# PWR_ICs.net
KiCad netlist of a schematic drawn in Altium Designer
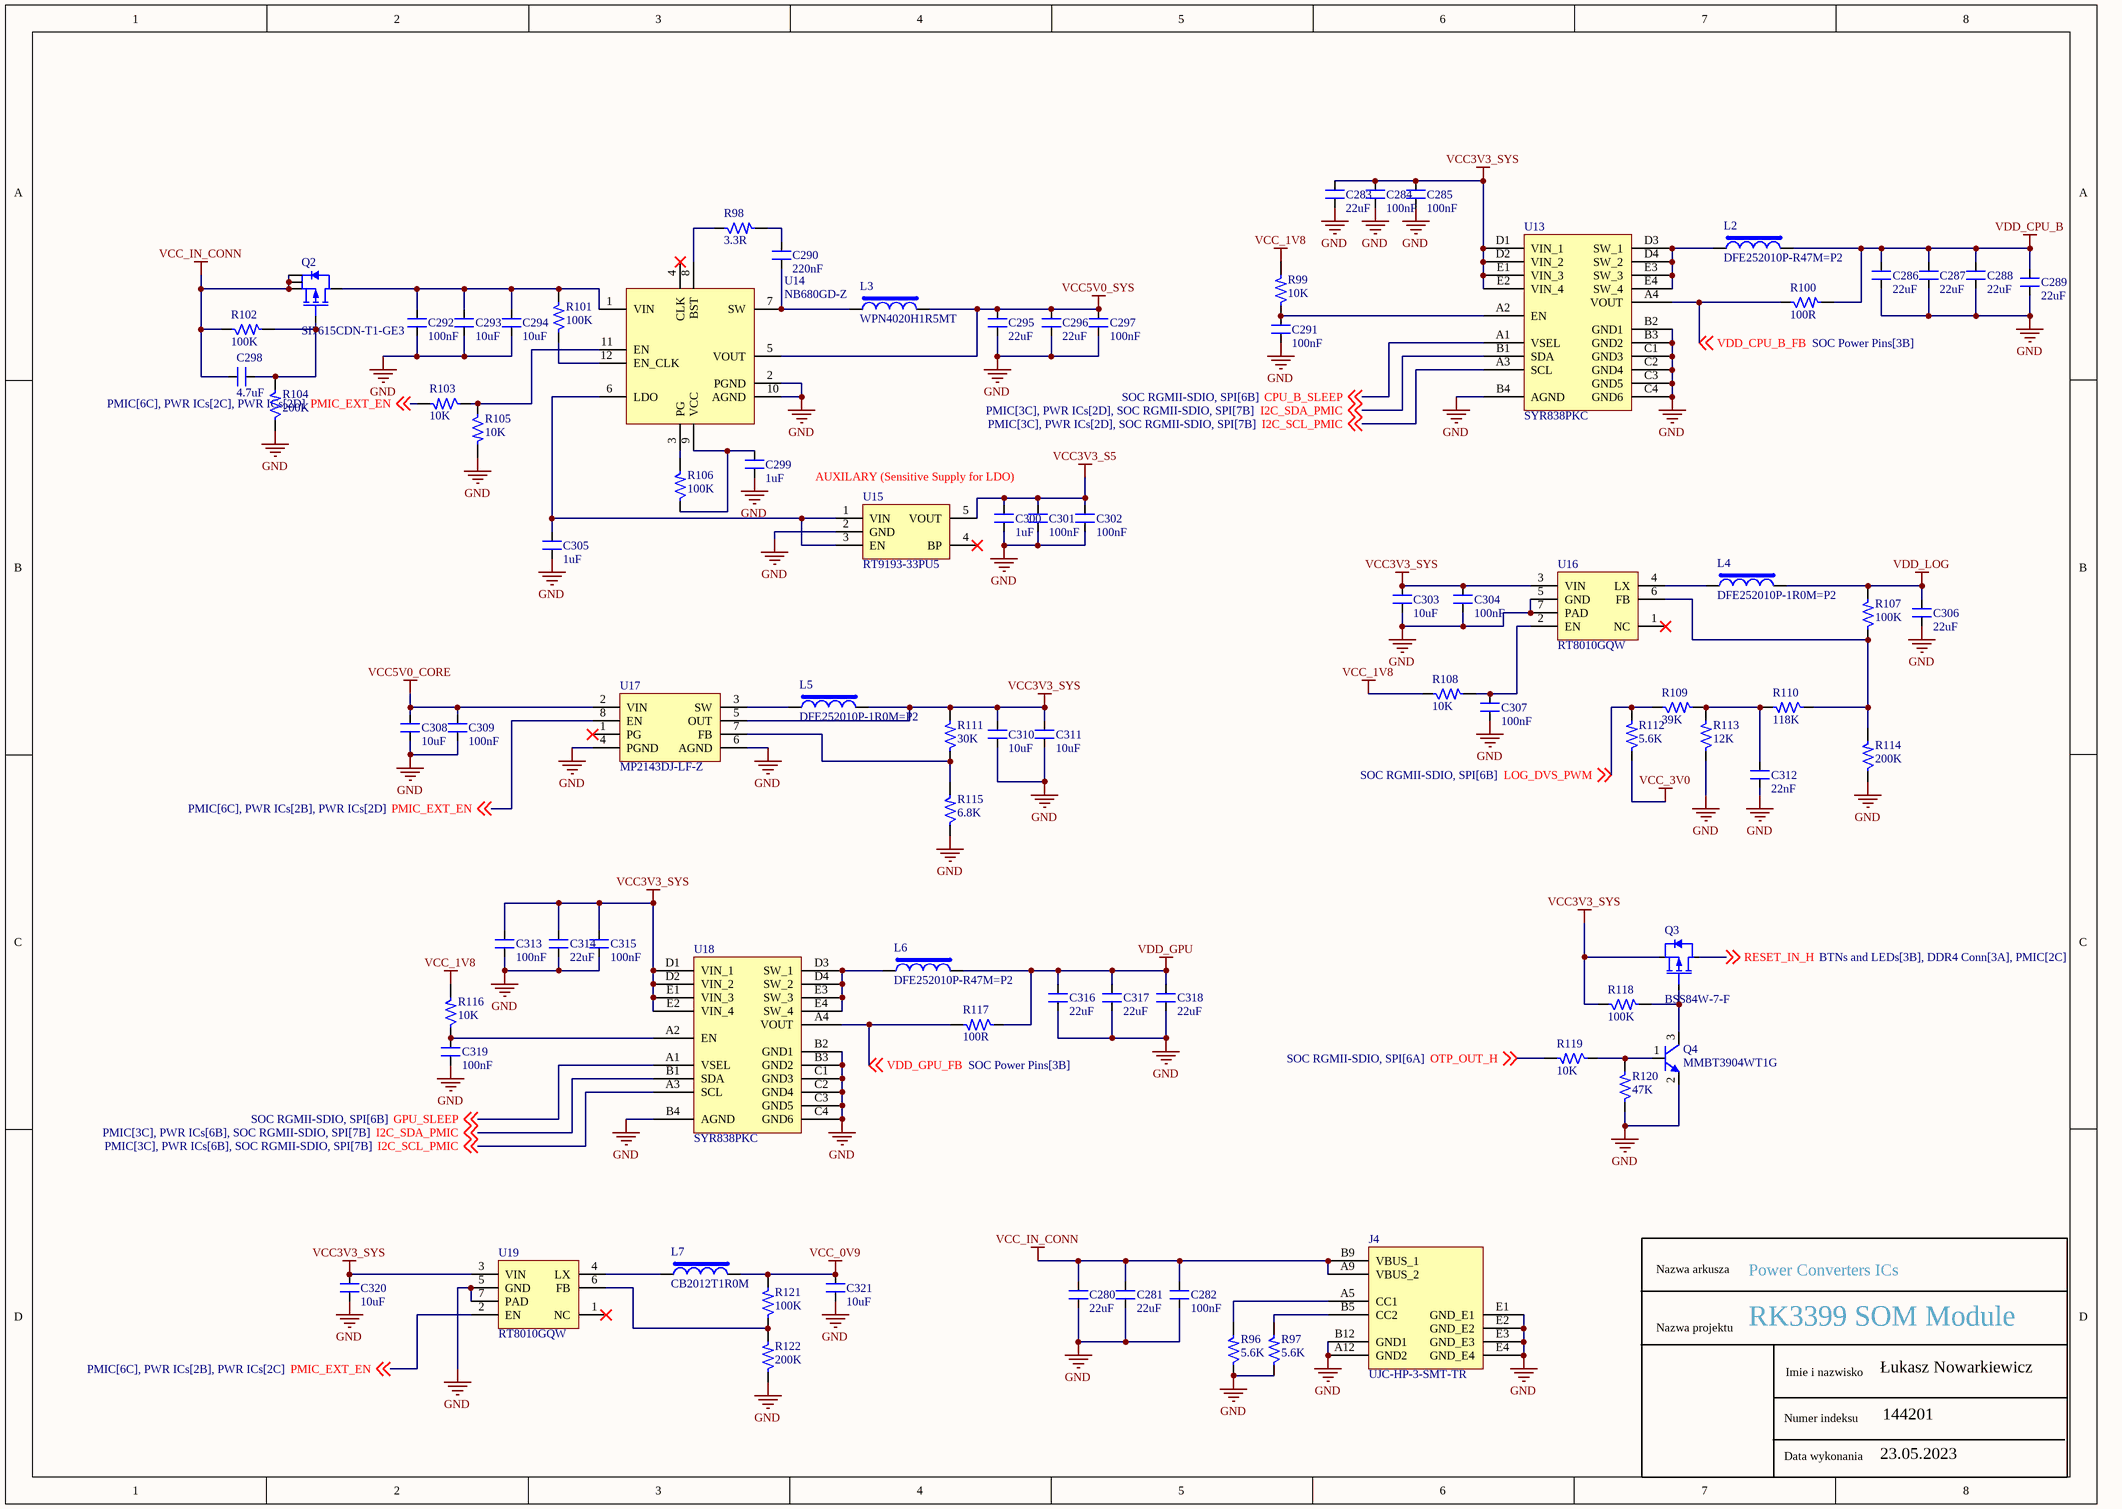
[diagram p0: PWR ICs.SchDoc]

(export (version "E")
  (design (tool "Eeschema 10.0.6"))
  (components
    (comp (ref "C280")
      (value "22uF")
      (footprint "CAP_0603")
      (description "22µF ±20% 10V Ceramic Capacitor X5R 0603 (1608 Metric)")
      (fields
        (field (name "MANUFACTURER") "Murata Electronics")
        (field (name "MANUFACTURER PART NUMBER") "GRM188R61A226ME15D")
      )
      (libsource (lib "RK3399 _Module_Schlib") (part "CAP_22uF-10V-20%-0603"))
    )
    (comp (ref "C281")
      (value "22uF")
      (footprint "CAP_0603")
      (description "22µF ±20% 10V Ceramic Capacitor X5R 0603 (1608 Metric)")
      (fields
        (field (name "MANUFACTURER") "Murata Electronics")
        (field (name "MANUFACTURER PART NUMBER") "GRM188R61A226ME15D")
      )
      (libsource (lib "RK3399 _Module_Schlib") (part "CAP_22uF-10V-20%-0603"))
    )
    (comp (ref "C282")
      (value "100nF")
      (footprint "CAP_0402")
      (description "0.1µF ±10% 25V Ceramic Capacitor X7R 0402 (1005 Metric)")
      (fields
        (field (name "MANUFACTURER") "Walsin Technology Corporation")
        (field (name "MANUFACTURER PART NUMBER") "0402B104K250CT")
      )
      (libsource (lib "RK3399 _Module_Schlib") (part "CAP_100nF-25V-10%-0402"))
    )
    (comp (ref "C283")
      (value "22uF")
      (footprint "CAP_0603")
      (description "22µF ±20% 10V Ceramic Capacitor X5R 0603 (1608 Metric)")
      (fields
        (field (name "MANUFACTURER") "Murata Electronics")
        (field (name "MANUFACTURER PART NUMBER") "GRM188R61A226ME15D")
      )
      (libsource (lib "RK3399 _Module_Schlib") (part "CAP_22uF-10V-20%-0603"))
    )
    (comp (ref "C284")
      (value "100nF")
      (footprint "CAP_0402")
      (description "0.1µF ±10% 25V Ceramic Capacitor X7R 0402 (1005 Metric)")
      (fields
        (field (name "MANUFACTURER") "Walsin Technology Corporation")
        (field (name "MANUFACTURER PART NUMBER") "0402B104K250CT")
      )
      (libsource (lib "RK3399 _Module_Schlib") (part "CAP_100nF-25V-10%-0402"))
    )
    (comp (ref "C285")
      (value "100nF")
      (footprint "CAP_0402")
      (description "0.1µF ±10% 25V Ceramic Capacitor X7R 0402 (1005 Metric)")
      (fields
        (field (name "MANUFACTURER") "Walsin Technology Corporation")
        (field (name "MANUFACTURER PART NUMBER") "0402B104K250CT")
      )
      (libsource (lib "RK3399 _Module_Schlib") (part "CAP_100nF-25V-10%-0402"))
    )
    (comp (ref "C286")
      (value "22uF")
      (footprint "CAP_0603")
      (description "22µF ±20% 10V Ceramic Capacitor X5R 0603 (1608 Metric)")
      (fields
        (field (name "MANUFACTURER") "Murata Electronics")
        (field (name "MANUFACTURER PART NUMBER") "GRM188R61A226ME15D")
      )
      (libsource (lib "RK3399 _Module_Schlib") (part "CAP_22uF-10V-20%-0603"))
    )
    (comp (ref "C287")
      (value "22uF")
      (footprint "CAP_0603")
      (description "22µF ±20% 10V Ceramic Capacitor X5R 0603 (1608 Metric)")
      (fields
        (field (name "MANUFACTURER") "Murata Electronics")
        (field (name "MANUFACTURER PART NUMBER") "GRM188R61A226ME15D")
      )
      (libsource (lib "RK3399 _Module_Schlib") (part "CAP_22uF-10V-20%-0603"))
    )
    (comp (ref "C288")
      (value "22uF")
      (footprint "CAP_0603")
      (description "22µF ±20% 10V Ceramic Capacitor X5R 0603 (1608 Metric)")
      (fields
        (field (name "MANUFACTURER") "Murata Electronics")
        (field (name "MANUFACTURER PART NUMBER") "GRM188R61A226ME15D")
      )
      (libsource (lib "RK3399 _Module_Schlib") (part "CAP_22uF-10V-20%-0603"))
    )
    (comp (ref "C289")
      (value "22uF")
      (footprint "CAP_0603")
      (description "22µF ±20% 10V Ceramic Capacitor X5R 0603 (1608 Metric)")
      (fields
        (field (name "MANUFACTURER") "Murata Electronics")
        (field (name "MANUFACTURER PART NUMBER") "GRM188R61A226ME15D")
      )
      (libsource (lib "RK3399 _Module_Schlib") (part "CAP_22uF-10V-20%-0603"))
    )
    (comp (ref "C290")
      (value "220nF")
      (footprint "CAP_0402")
      (description "0.22µF ±10% 10V Ceramic Capacitor X7R 0402 (1005 Metric)")
      (fields
        (field (name "MANUFACTURER") "Samsung Electro-Mechanics")
        (field (name "MANUFACTURER PART NUMBER") "CL05B224KP5NNNC")
      )
      (libsource (lib "RK3399 _Module_Schlib") (part "CAP_220nF-10V-10%-0402"))
    )
    (comp (ref "C291")
      (value "100nF")
      (footprint "CAP_0402")
      (description "0.1µF ±10% 25V Ceramic Capacitor X7R 0402 (1005 Metric)")
      (fields
        (field (name "MANUFACTURER") "Walsin Technology Corporation")
        (field (name "MANUFACTURER PART NUMBER") "0402B104K250CT")
      )
      (libsource (lib "RK3399 _Module_Schlib") (part "CAP_100nF-25V-10%-0402"))
    )
    (comp (ref "C292")
      (value "100nF")
      (footprint "CAP_0402")
      (description "0.1µF ±10% 25V Ceramic Capacitor X7R 0402 (1005 Metric)")
      (fields
        (field (name "MANUFACTURER") "Walsin Technology Corporation")
        (field (name "MANUFACTURER PART NUMBER") "0402B104K250CT")
      )
      (libsource (lib "RK3399 _Module_Schlib") (part "CAP_100nF-25V-10%-0402"))
    )
    (comp (ref "C293")
      (value "10uF")
      (footprint "CAP_0402")
      (description "10µF ±20% 10V Ceramic Capacitor X5R 0402 (1005 Metric)")
      (fields
        (field (name "MANUFACTURER PART NUMBER") "CL05A106MP5NUNC")
        (field (name "MANUFACTURER") "Samsung Electro-Mechanics")
      )
      (libsource (lib "RK3399 _Module_Schlib") (part "CAP_10uF-10V-20%-0402"))
    )
    (comp (ref "C294")
      (value "10uF")
      (footprint "CAP_0402")
      (description "10µF ±20% 10V Ceramic Capacitor X5R 0402 (1005 Metric)")
      (fields
        (field (name "MANUFACTURER PART NUMBER") "CL05A106MP5NUNC")
        (field (name "MANUFACTURER") "Samsung Electro-Mechanics")
      )
      (libsource (lib "RK3399 _Module_Schlib") (part "CAP_10uF-10V-20%-0402"))
    )
    (comp (ref "C295")
      (value "22uF")
      (footprint "CAP_0603")
      (description "22µF ±20% 10V Ceramic Capacitor X5R 0603 (1608 Metric)")
      (fields
        (field (name "MANUFACTURER") "Murata Electronics")
        (field (name "MANUFACTURER PART NUMBER") "GRM188R61A226ME15D")
      )
      (libsource (lib "RK3399 _Module_Schlib") (part "CAP_22uF-10V-20%-0603"))
    )
    (comp (ref "C296")
      (value "22uF")
      (footprint "CAP_0603")
      (description "22µF ±20% 10V Ceramic Capacitor X5R 0603 (1608 Metric)")
      (fields
        (field (name "MANUFACTURER") "Murata Electronics")
        (field (name "MANUFACTURER PART NUMBER") "GRM188R61A226ME15D")
      )
      (libsource (lib "RK3399 _Module_Schlib") (part "CAP_22uF-10V-20%-0603"))
    )
    (comp (ref "C297")
      (value "100nF")
      (footprint "CAP_0402")
      (description "0.1µF ±10% 25V Ceramic Capacitor X7R 0402 (1005 Metric)")
      (fields
        (field (name "MANUFACTURER") "Walsin Technology Corporation")
        (field (name "MANUFACTURER PART NUMBER") "0402B104K250CT")
      )
      (libsource (lib "RK3399 _Module_Schlib") (part "CAP_100nF-25V-10%-0402"))
    )
    (comp (ref "C298")
      (value "4.7uF")
      (footprint "CAP_0402")
      (description "4.7µF ±10% 10V Ceramic Capacitor X5R 0402 (1005 Metric)")
      (fields
        (field (name "MANUFACTURER") "Samsung Electro-Mechanics")
        (field (name "MANUFACTURER PART NUMBER") "CL05A475KP5NRNC")
      )
      (libsource (lib "RK3399 _Module_Schlib") (part "CAP_4.7uF-10V-10%-0402"))
    )
    (comp (ref "C299")
      (value "1uF")
      (footprint "CAP_0402")
      (description "1µF ±10% 16V Ceramic Capacitor X5R 0402 (1005 Metric)")
      (fields
        (field (name "MANUFACTURER") "Knowles Novacap")
        (field (name "MANUFACTURER PART NUMBER") "0402BW105K160YT")
      )
      (libsource (lib "RK3399 _Module_Schlib") (part "CAP_1uF-16V-10%-0402"))
    )
    (comp (ref "C300")
      (value "1uF")
      (footprint "CAP_0402")
      (description "1µF ±10% 16V Ceramic Capacitor X5R 0402 (1005 Metric)")
      (fields
        (field (name "MANUFACTURER") "Knowles Novacap")
        (field (name "MANUFACTURER PART NUMBER") "0402BW105K160YT")
      )
      (libsource (lib "RK3399 _Module_Schlib") (part "CAP_1uF-16V-10%-0402"))
    )
    (comp (ref "C301")
      (value "100nF")
      (footprint "CAP_0402")
      (description "0.1µF ±10% 25V Ceramic Capacitor X7R 0402 (1005 Metric)")
      (fields
        (field (name "MANUFACTURER") "Walsin Technology Corporation")
        (field (name "MANUFACTURER PART NUMBER") "0402B104K250CT")
      )
      (libsource (lib "RK3399 _Module_Schlib") (part "CAP_100nF-25V-10%-0402"))
    )
    (comp (ref "C302")
      (value "100nF")
      (footprint "CAP_0402")
      (description "0.1µF ±10% 25V Ceramic Capacitor X7R 0402 (1005 Metric)")
      (fields
        (field (name "MANUFACTURER") "Walsin Technology Corporation")
        (field (name "MANUFACTURER PART NUMBER") "0402B104K250CT")
      )
      (libsource (lib "RK3399 _Module_Schlib") (part "CAP_100nF-25V-10%-0402"))
    )
    (comp (ref "C303")
      (value "10uF")
      (footprint "CAP_0402")
      (description "10µF ±20% 10V Ceramic Capacitor X5R 0402 (1005 Metric)")
      (fields
        (field (name "MANUFACTURER PART NUMBER") "CL05A106MP5NUNC")
        (field (name "MANUFACTURER") "Samsung Electro-Mechanics")
      )
      (libsource (lib "RK3399 _Module_Schlib") (part "CAP_10uF-10V-20%-0402"))
    )
    (comp (ref "C304")
      (value "100nF")
      (footprint "CAP_0402")
      (description "0.1µF ±10% 25V Ceramic Capacitor X7R 0402 (1005 Metric)")
      (fields
        (field (name "MANUFACTURER") "Walsin Technology Corporation")
        (field (name "MANUFACTURER PART NUMBER") "0402B104K250CT")
      )
      (libsource (lib "RK3399 _Module_Schlib") (part "CAP_100nF-25V-10%-0402"))
    )
    (comp (ref "C305")
      (value "1uF")
      (footprint "CAP_0402")
      (description "1µF ±10% 16V Ceramic Capacitor X5R 0402 (1005 Metric)")
      (fields
        (field (name "MANUFACTURER") "Knowles Novacap")
        (field (name "MANUFACTURER PART NUMBER") "0402BW105K160YT")
      )
      (libsource (lib "RK3399 _Module_Schlib") (part "CAP_1uF-16V-10%-0402"))
    )
    (comp (ref "C306")
      (value "22uF")
      (footprint "CAP_0603")
      (description "22µF ±20% 10V Ceramic Capacitor X5R 0603 (1608 Metric)")
      (fields
        (field (name "MANUFACTURER") "Murata Electronics")
        (field (name "MANUFACTURER PART NUMBER") "GRM188R61A226ME15D")
      )
      (libsource (lib "RK3399 _Module_Schlib") (part "CAP_22uF-10V-20%-0603"))
    )
    (comp (ref "C307")
      (value "100nF")
      (footprint "CAP_0402")
      (description "0.1µF ±10% 25V Ceramic Capacitor X7R 0402 (1005 Metric)")
      (fields
        (field (name "MANUFACTURER") "Walsin Technology Corporation")
        (field (name "MANUFACTURER PART NUMBER") "0402B104K250CT")
      )
      (libsource (lib "RK3399 _Module_Schlib") (part "CAP_100nF-25V-10%-0402"))
    )
    (comp (ref "C308")
      (value "10uF")
      (footprint "CAP_0402")
      (description "10µF ±20% 10V Ceramic Capacitor X5R 0402 (1005 Metric)")
      (fields
        (field (name "MANUFACTURER PART NUMBER") "CL05A106MP5NUNC")
        (field (name "MANUFACTURER") "Samsung Electro-Mechanics")
      )
      (libsource (lib "RK3399 _Module_Schlib") (part "CAP_10uF-10V-20%-0402"))
    )
    (comp (ref "C309")
      (value "100nF")
      (footprint "CAP_0402")
      (description "0.1µF ±10% 25V Ceramic Capacitor X7R 0402 (1005 Metric)")
      (fields
        (field (name "MANUFACTURER") "Walsin Technology Corporation")
        (field (name "MANUFACTURER PART NUMBER") "0402B104K250CT")
      )
      (libsource (lib "RK3399 _Module_Schlib") (part "CAP_100nF-25V-10%-0402"))
    )
    (comp (ref "C310")
      (value "10uF")
      (footprint "CAP_0402")
      (description "10µF ±20% 10V Ceramic Capacitor X5R 0402 (1005 Metric)")
      (fields
        (field (name "MANUFACTURER PART NUMBER") "CL05A106MP5NUNC")
        (field (name "MANUFACTURER") "Samsung Electro-Mechanics")
      )
      (libsource (lib "RK3399 _Module_Schlib") (part "CAP_10uF-10V-20%-0402"))
    )
    (comp (ref "C311")
      (value "10uF")
      (footprint "CAP_0402")
      (description "10µF ±20% 10V Ceramic Capacitor X5R 0402 (1005 Metric)")
      (fields
        (field (name "MANUFACTURER PART NUMBER") "CL05A106MP5NUNC")
        (field (name "MANUFACTURER") "Samsung Electro-Mechanics")
      )
      (libsource (lib "RK3399 _Module_Schlib") (part "CAP_10uF-10V-20%-0402"))
    )
    (comp (ref "C312")
      (value "22nF")
      (footprint "CAP_0402")
      (description "0.022µF ±10% 10V Ceramic Capacitor X7R 0402 (1005 Metric)")
      (fields
        (field (name "MANUFACTURER") "Samsung Electro-Mechanics")
        (field (name "MANUFACTURER PART NUMBER") "CL05B223KP5NNNC")
      )
      (libsource (lib "RK3399 _Module_Schlib") (part "CAP_22nF-10V-10%-0402"))
    )
    (comp (ref "C313")
      (value "100nF")
      (footprint "CAP_0402")
      (description "0.1µF ±10% 25V Ceramic Capacitor X7R 0402 (1005 Metric)")
      (fields
        (field (name "MANUFACTURER") "Walsin Technology Corporation")
        (field (name "MANUFACTURER PART NUMBER") "0402B104K250CT")
      )
      (libsource (lib "RK3399 _Module_Schlib") (part "CAP_100nF-25V-10%-0402"))
    )
    (comp (ref "C314")
      (value "22uF")
      (footprint "CAP_0603")
      (description "22µF ±20% 10V Ceramic Capacitor X5R 0603 (1608 Metric)")
      (fields
        (field (name "MANUFACTURER") "Murata Electronics")
        (field (name "MANUFACTURER PART NUMBER") "GRM188R61A226ME15D")
      )
      (libsource (lib "RK3399 _Module_Schlib") (part "CAP_22uF-10V-20%-0603"))
    )
    (comp (ref "C315")
      (value "100nF")
      (footprint "CAP_0402")
      (description "0.1µF ±10% 25V Ceramic Capacitor X7R 0402 (1005 Metric)")
      (fields
        (field (name "MANUFACTURER") "Walsin Technology Corporation")
        (field (name "MANUFACTURER PART NUMBER") "0402B104K250CT")
      )
      (libsource (lib "RK3399 _Module_Schlib") (part "CAP_100nF-25V-10%-0402"))
    )
    (comp (ref "C316")
      (value "22uF")
      (footprint "CAP_0603")
      (description "22µF ±20% 10V Ceramic Capacitor X5R 0603 (1608 Metric)")
      (fields
        (field (name "MANUFACTURER") "Murata Electronics")
        (field (name "MANUFACTURER PART NUMBER") "GRM188R61A226ME15D")
      )
      (libsource (lib "RK3399 _Module_Schlib") (part "CAP_22uF-10V-20%-0603"))
    )
    (comp (ref "C317")
      (value "22uF")
      (footprint "CAP_0603")
      (description "22µF ±20% 10V Ceramic Capacitor X5R 0603 (1608 Metric)")
      (fields
        (field (name "MANUFACTURER") "Murata Electronics")
        (field (name "MANUFACTURER PART NUMBER") "GRM188R61A226ME15D")
      )
      (libsource (lib "RK3399 _Module_Schlib") (part "CAP_22uF-10V-20%-0603"))
    )
    (comp (ref "C318")
      (value "22uF")
      (footprint "CAP_0603")
      (description "22µF ±20% 10V Ceramic Capacitor X5R 0603 (1608 Metric)")
      (fields
        (field (name "MANUFACTURER") "Murata Electronics")
        (field (name "MANUFACTURER PART NUMBER") "GRM188R61A226ME15D")
      )
      (libsource (lib "RK3399 _Module_Schlib") (part "CAP_22uF-10V-20%-0603"))
    )
    (comp (ref "C319")
      (value "100nF")
      (footprint "CAP_0402")
      (description "0.1µF ±10% 25V Ceramic Capacitor X7R 0402 (1005 Metric)")
      (fields
        (field (name "MANUFACTURER") "Walsin Technology Corporation")
        (field (name "MANUFACTURER PART NUMBER") "0402B104K250CT")
      )
      (libsource (lib "RK3399 _Module_Schlib") (part "CAP_100nF-25V-10%-0402"))
    )
    (comp (ref "C320")
      (value "10uF")
      (footprint "CAP_0402")
      (description "10µF ±20% 10V Ceramic Capacitor X5R 0402 (1005 Metric)")
      (fields
        (field (name "MANUFACTURER PART NUMBER") "CL05A106MP5NUNC")
        (field (name "MANUFACTURER") "Samsung Electro-Mechanics")
      )
      (libsource (lib "RK3399 _Module_Schlib") (part "CAP_10uF-10V-20%-0402"))
    )
    (comp (ref "C321")
      (value "10uF")
      (footprint "CAP_0402")
      (description "10µF ±20% 10V Ceramic Capacitor X5R 0402 (1005 Metric)")
      (fields
        (field (name "MANUFACTURER PART NUMBER") "CL05A106MP5NUNC")
        (field (name "MANUFACTURER") "Samsung Electro-Mechanics")
      )
      (libsource (lib "RK3399 _Module_Schlib") (part "CAP_10uF-10V-20%-0402"))
    )
    (comp (ref "J4")
      (value "UJC-HP-3-SMT-TR")
      (footprint "CON6_48.4_UJC-HP-3-SMT-TR")
      (fields (field (name "MANUFACTURER") "CUI Devices"))
      (libsource (lib "RK3399 _Module_Schlib") (part "CON-TYPEC_6X1-100-RA-TH"))
    )
    (comp (ref "L2")
      (value "DFE252010P-R47M=P2")
      (footprint "IND_1008")
      (description "470nH Shielded Wirewound Inductor 5A 35mOhm Max 1008 (2520 Metric)")
      (fields (field (name "MANUFACTURER") "Murata Electronics"))
      (libsource (lib "RK3399 _Module_Schlib") (part "IND_470nH-5A-20%-1008"))
    )
    (comp (ref "L3")
      (value "WPN4020H1R5MT")
      (footprint "IND_1616")
      (fields (field (name "MANUFACTURER") "Sunlord"))
      (libsource (lib "RK3399 _Module_Schlib") (part "IND_1.5uH-6A-20%-SMD"))
    )
    (comp (ref "L4")
      (value "DFE252010P-1R0M=P2")
      (footprint "IND_1008")
      (description "1µH Shielded Wirewound Inductor 3.8A 54mOhm Max 1008 (2520 Metric)")
      (fields (field (name "MANUFACTURER") "Murata Electronics"))
      (libsource (lib "RK3399 _Module_Schlib") (part "IND_1uH-3.8A-20%-1008"))
    )
    (comp (ref "L5")
      (value "DFE252010P-1R0M=P2")
      (footprint "IND_1008")
      (description "1µH Shielded Wirewound Inductor 3.8A 54mOhm Max 1008 (2520 Metric)")
      (fields (field (name "MANUFACTURER") "Murata Electronics"))
      (libsource (lib "RK3399 _Module_Schlib") (part "IND_1uH-3.8A-20%-1008"))
    )
    (comp (ref "L6")
      (value "DFE252010P-R47M=P2")
      (footprint "IND_1008")
      (description "470nH Shielded Wirewound Inductor 5A 35mOhm Max 1008 (2520 Metric)")
      (fields (field (name "MANUFACTURER") "Murata Electronics"))
      (libsource (lib "RK3399 _Module_Schlib") (part "IND_470nH-5A-20%-1008"))
    )
    (comp (ref "L7")
      (value "CB2012T1R0M")
      (footprint "IND_0805")
      (description "1uH ±20% 500mA 150mΩ 0805 Inductors (SMD) RoHS")
      (fields (field (name "MANUFACTURER") "Taiyo Yuden"))
      (libsource (lib "RK3399 _Module_Schlib") (part "IND_1uF-0.5A-20%-0805"))
    )
    (comp (ref "Q2")
      (value "SI7615CDN-T1-GE3")
      (footprint "PowerPAK_1212-8_SMD")
      (description "P-Channel 20V 35A (Tc) 33W (Tc) Surface Mount PowerPAK® 1212-8")
      (fields (field (name "MANUFACTURER") "Vishay Siliconix"))
      (libsource (lib "RK3399 _Module_Schlib") (part "MOSFET-P_20V-35A-1212-8"))
    )
    (comp (ref "Q3")
      (value "BSS84W-7-F")
      (footprint "SOT-323-3")
      (description "P-Channel 50V 130mA (Ta) 200mW (Ta) Surface Mount SOT-323")
      (fields (field (name "MANUFACTURER") "Diodes Incorporated"))
      (libsource (lib "RK3399 _Module_Schlib") (part "MOSFET-P_50V-130mA-SOT-323"))
    )
    (comp (ref "Q4")
      (value "MMBT3904WT1G")
      (footprint "SOT-323-3")
      (description "Bipolar Transistors - BJT 200mA 60V NPN")
      (fields (field (name "MANUFACTURER") "ON Semiconductor"))
      (libsource (lib "RK3399 _Module_Schlib") (part "TRNS-NPN_60V-0.2A-SOT323"))
    )
    (comp (ref "R96")
      (value "5.6K")
      (footprint "RES_0402")
      (fields
        (field (name "MANUFACTURER") "KOA Speer Electronics, Inc.")
        (field (name "MANUFACTURER PART NUMBER") "RK73H1ETTP5601F")
      )
      (libsource (lib "RK3399 _Module_Schlib") (part "RES_5.6K-0.1W-1%-0402"))
    )
    (comp (ref "R97")
      (value "5.6K")
      (footprint "RES_0402")
      (fields
        (field (name "MANUFACTURER") "KOA Speer Electronics, Inc.")
        (field (name "MANUFACTURER PART NUMBER") "RK73H1ETTP5601F")
      )
      (libsource (lib "RK3399 _Module_Schlib") (part "RES_5.6K-0.1W-1%-0402"))
    )
    (comp (ref "R98")
      (value "3.3R")
      (footprint "RES_0402")
      (fields
        (field (name "MANUFACTURER") "Panasonic Electronic Components")
        (field (name "MANUFACTURER PART NUMBER") "ERJ-U02F3R30X")
      )
      (libsource (lib "RK3399 _Module_Schlib") (part "RES_3.3R-0.1W-1%-0402"))
    )
    (comp (ref "R99")
      (value "10K")
      (footprint "RES_0402")
      (description "10 kOhms ±1% 0.1W, 1/10W Chip Resistor 0402 (1005 Metric) Anti-Sulfur Thin Film")
      (fields
        (field (name "MANUFACTURER") "Vishay Beyschlag/Draloric/BC Components")
        (field (name "MANUFACTURER PART NUMBER") "MCS04020C1002FE000")
      )
      (libsource (lib "RK3399 _Module_Schlib") (part "RES_10K-0.1W-1%-0402"))
    )
    (comp (ref "R100")
      (value "100R")
      (footprint "RES_0402")
      (fields
        (field (name "MANUFACTURER") "KOA Speer Electronics, Inc.")
        (field (name "MANUFACTURER PART NUMBER") "RK73H1ETTP1000F")
      )
      (libsource (lib "RK3399 _Module_Schlib") (part "RES_100R-0.1W-1%-0402"))
    )
    (comp (ref "R101")
      (value "100K")
      (footprint "RES_0402")
      (description "100 kOhms ±1% 0.1W, 1/10W Chip Resistor 0402 (1005 Metric) Anti-Sulfur Thin Film")
      (fields
        (field (name "MANUFACTURER") "Vishay Beyschlag/Draloric/BC Components")
        (field (name "MANUFACTURER PART NUMBER") "MCS04020C1003FE000")
      )
      (libsource (lib "RK3399 _Module_Schlib") (part "RES_100K-0.1W-1%-0402"))
    )
    (comp (ref "R102")
      (value "100K")
      (footprint "RES_0402")
      (description "100 kOhms ±1% 0.1W, 1/10W Chip Resistor 0402 (1005 Metric) Anti-Sulfur Thin Film")
      (fields
        (field (name "MANUFACTURER") "Vishay Beyschlag/Draloric/BC Components")
        (field (name "MANUFACTURER PART NUMBER") "MCS04020C1003FE000")
      )
      (libsource (lib "RK3399 _Module_Schlib") (part "RES_100K-0.1W-1%-0402"))
    )
    (comp (ref "R103")
      (value "10K")
      (footprint "RES_0402")
      (description "10 kOhms ±1% 0.1W, 1/10W Chip Resistor 0402 (1005 Metric) Anti-Sulfur Thin Film")
      (fields
        (field (name "MANUFACTURER") "Vishay Beyschlag/Draloric/BC Components")
        (field (name "MANUFACTURER PART NUMBER") "MCS04020C1002FE000")
      )
      (libsource (lib "RK3399 _Module_Schlib") (part "RES_10K-0.1W-1%-0402"))
    )
    (comp (ref "R104")
      (value "200K")
      (footprint "RES_0402")
      (description "200 kOhms ±1% 0.1W, 1/10W Chip Resistor 0402 (1005 Metric) Automotive AEC-Q200 Thick Film")
      (fields
        (field (name "MANUFACTURER") "Panasonic Electronic Components")
        (field (name "MANUFACTURER PART NUMBER") "ERJ-2RKF2003X")
      )
      (libsource (lib "RK3399 _Module_Schlib") (part "RES_200K-0.1W-1%-0402"))
    )
    (comp (ref "R105")
      (value "10K")
      (footprint "RES_0402")
      (description "10 kOhms ±1% 0.1W, 1/10W Chip Resistor 0402 (1005 Metric) Anti-Sulfur Thin Film")
      (fields
        (field (name "MANUFACTURER") "Vishay Beyschlag/Draloric/BC Components")
        (field (name "MANUFACTURER PART NUMBER") "MCS04020C1002FE000")
      )
      (libsource (lib "RK3399 _Module_Schlib") (part "RES_10K-0.1W-1%-0402"))
    )
    (comp (ref "R106")
      (value "100K")
      (footprint "RES_0402")
      (description "100 kOhms ±1% 0.1W, 1/10W Chip Resistor 0402 (1005 Metric) Anti-Sulfur Thin Film")
      (fields
        (field (name "MANUFACTURER") "Vishay Beyschlag/Draloric/BC Components")
        (field (name "MANUFACTURER PART NUMBER") "MCS04020C1003FE000")
      )
      (libsource (lib "RK3399 _Module_Schlib") (part "RES_100K-0.1W-1%-0402"))
    )
    (comp (ref "R107")
      (value "100K")
      (footprint "RES_0402")
      (description "100 kOhms ±1% 0.1W, 1/10W Chip Resistor 0402 (1005 Metric) Anti-Sulfur Thin Film")
      (fields
        (field (name "MANUFACTURER") "Vishay Beyschlag/Draloric/BC Components")
        (field (name "MANUFACTURER PART NUMBER") "MCS04020C1003FE000")
      )
      (libsource (lib "RK3399 _Module_Schlib") (part "RES_100K-0.1W-1%-0402"))
    )
    (comp (ref "R108")
      (value "10K")
      (footprint "RES_0402")
      (description "10 kOhms ±1% 0.1W, 1/10W Chip Resistor 0402 (1005 Metric) Anti-Sulfur Thin Film")
      (fields
        (field (name "MANUFACTURER") "Vishay Beyschlag/Draloric/BC Components")
        (field (name "MANUFACTURER PART NUMBER") "MCS04020C1002FE000")
      )
      (libsource (lib "RK3399 _Module_Schlib") (part "RES_10K-0.1W-1%-0402"))
    )
    (comp (ref "R109")
      (value "39K")
      (footprint "RES_0402")
      (fields
        (field (name "MANUFACTURER") "KOA Speer Electronics, Inc.")
        (field (name "MANUFACTURER PART NUMBER") "RK73H1ETTP3902F")
      )
      (libsource (lib "RK3399 _Module_Schlib") (part "RES_39K-0.1W-1%-0402"))
    )
    (comp (ref "R110")
      (value "118K")
      (footprint "RES_0402")
      (fields
        (field (name "MANUFACTURER") "KOA Speer Electronics, Inc.")
        (field (name "MANUAFCTURER PART NUMBER") "RK73H1ETTP1183F")
      )
      (libsource (lib "RK3399 _Module_Schlib") (part "RES_118K-0.1W-1%-0402"))
    )
    (comp (ref "R111")
      (value "30K")
      (footprint "RES_0402")
      (fields
        (field (name "MANUFACTURER") "KOA Speer Electronics, Inc.")
        (field (name "MANUFACTURER PART NUMBER") "RK73H1ETTP3002F")
      )
      (libsource (lib "RK3399 _Module_Schlib") (part "RES_30K-0.1W-1%-0402"))
    )
    (comp (ref "R112")
      (value "5.6K")
      (footprint "RES_0402")
      (fields
        (field (name "MANUFACTURER") "KOA Speer Electronics, Inc.")
        (field (name "MANUFACTURER PART NUMBER") "RK73H1ETTP5601F")
      )
      (libsource (lib "RK3399 _Module_Schlib") (part "RES_5.6K-0.1W-1%-0402"))
    )
    (comp (ref "R113")
      (value "12K")
      (footprint "RES_0402")
      (description "12 kOhms ±1% 0.1W, 1/10W Chip Resistor 0402 (1005 Metric) Anti-Sulfur Thin Film")
      (fields
        (field (name "MANUFACTURER") "Vishay Beyschlag/Draloric/BC Components")
        (field (name "MANUFACTURER PART NUMBER") "MCS04020C1202FE000")
      )
      (libsource (lib "RK3399 _Module_Schlib") (part "RES_12K-0.1W-1%-0402"))
    )
    (comp (ref "R114")
      (value "200K")
      (footprint "RES_0402")
      (description "200 kOhms ±1% 0.1W, 1/10W Chip Resistor 0402 (1005 Metric) Automotive AEC-Q200 Thick Film")
      (fields
        (field (name "MANUFACTURER") "Panasonic Electronic Components")
        (field (name "MANUFACTURER PART NUMBER") "ERJ-2RKF2003X")
      )
      (libsource (lib "RK3399 _Module_Schlib") (part "RES_200K-0.1W-1%-0402"))
    )
    (comp (ref "R115")
      (value "6.8K")
      (footprint "RES_0402")
      (description "6.8 kOhms ±1% 0.1W, 1/10W Chip Resistor 0402 (1005 Metric) Anti-Sulfur Thin Film")
      (fields
        (field (name "MANUFACTURER PART NUMBER") "MCS04020C6801FE000")
        (field (name "MANUFACTURER") "Vishay Beyschlag/Draloric/BC Components")
      )
      (libsource (lib "RK3399 _Module_Schlib") (part "RES_6.8K-0.1W-1%-0402"))
    )
    (comp (ref "R116")
      (value "10K")
      (footprint "RES_0402")
      (description "10 kOhms ±1% 0.1W, 1/10W Chip Resistor 0402 (1005 Metric) Anti-Sulfur Thin Film")
      (fields
        (field (name "MANUFACTURER") "Vishay Beyschlag/Draloric/BC Components")
        (field (name "MANUFACTURER PART NUMBER") "MCS04020C1002FE000")
      )
      (libsource (lib "RK3399 _Module_Schlib") (part "RES_10K-0.1W-1%-0402"))
    )
    (comp (ref "R117")
      (value "100R")
      (footprint "RES_0402")
      (fields
        (field (name "MANUFACTURER") "KOA Speer Electronics, Inc.")
        (field (name "MANUFACTURER PART NUMBER") "RK73H1ETTP1000F")
      )
      (libsource (lib "RK3399 _Module_Schlib") (part "RES_100R-0.1W-1%-0402"))
    )
    (comp (ref "R118")
      (value "100K")
      (footprint "RES_0402")
      (description "100 kOhms ±1% 0.1W, 1/10W Chip Resistor 0402 (1005 Metric) Anti-Sulfur Thin Film")
      (fields
        (field (name "MANUFACTURER") "Vishay Beyschlag/Draloric/BC Components")
        (field (name "MANUFACTURER PART NUMBER") "MCS04020C1003FE000")
      )
      (libsource (lib "RK3399 _Module_Schlib") (part "RES_100K-0.1W-1%-0402"))
    )
    (comp (ref "R119")
      (value "10K")
      (footprint "RES_0402")
      (description "10 kOhms ±1% 0.1W, 1/10W Chip Resistor 0402 (1005 Metric) Anti-Sulfur Thin Film")
      (fields
        (field (name "MANUFACTURER") "Vishay Beyschlag/Draloric/BC Components")
        (field (name "MANUFACTURER PART NUMBER") "MCS04020C1002FE000")
      )
      (libsource (lib "RK3399 _Module_Schlib") (part "RES_10K-0.1W-1%-0402"))
    )
    (comp (ref "R120")
      (value "47K")
      (footprint "RES_0402")
      (description "47 kOhms ±1% 0.1W, 1/10W Chip Resistor 0402 (1005 Metric) Automotive AEC-Q200 Thick Film")
      (fields
        (field (name "MANUFACTURER") "Panasonic Electronic Components")
        (field (name "MANUFACTURER PART NUMBER") "ERJ-2RKF4702X")
      )
      (libsource (lib "RK3399 _Module_Schlib") (part "RES_47K-0.1W-1%-0402"))
    )
    (comp (ref "R121")
      (value "100K")
      (footprint "RES_0402")
      (description "100 kOhms ±1% 0.1W, 1/10W Chip Resistor 0402 (1005 Metric) Anti-Sulfur Thin Film")
      (fields
        (field (name "MANUFACTURER") "Vishay Beyschlag/Draloric/BC Components")
        (field (name "MANUFACTURER PART NUMBER") "MCS04020C1003FE000")
      )
      (libsource (lib "RK3399 _Module_Schlib") (part "RES_100K-0.1W-1%-0402"))
    )
    (comp (ref "R122")
      (value "200K")
      (footprint "RES_0402")
      (description "200 kOhms ±1% 0.1W, 1/10W Chip Resistor 0402 (1005 Metric) Automotive AEC-Q200 Thick Film")
      (fields
        (field (name "MANUFACTURER") "Panasonic Electronic Components")
        (field (name "MANUFACTURER PART NUMBER") "ERJ-2RKF2003X")
      )
      (libsource (lib "RK3399 _Module_Schlib") (part "RES_200K-0.1W-1%-0402"))
    )
    (comp (ref "U13")
      (value "SYR838PKC")
      (footprint "CSP20_15.7_100x84_SMD")
      (description "Step-Down Positive Programmable 1 6A 2.4MHz CSP1.56*1.96-20 DC-DC Converters RoHS")
      (fields (field (name "MANUFACTURER") "Silergy Corp"))
      (libsource (lib "RK3399 _Module_Schlib") (part "IC_SYR838PKC"))
    )
    (comp (ref "U14")
      (value "NB680GD-Z")
      (footprint "QFN-12_19_118X118_SMD")
      (description "Switching Voltage Regulators 26V Fixed 3.3 V-8A Sync Buck Converter")
      (fields (field (name "MANUFACTURER") "Monolithic Power Systems (MPS)"))
      (libsource (lib "RK3399 _Module_Schlib") (part "REG_3.3V-26V-8A-QFN-12"))
    )
    (comp (ref "U15")
      (value "RT9193-33PU5")
      (footprint "SC70-5")
      (description "SC-70-5 Dropout Regulators(LDO) RoHS")
      (fields (field (name "MANUFACTURER") "Richtek Tech"))
      (libsource (lib "RK3399 _Module_Schlib") (part "REG_3.3V-5.5V-300mA-SC-70-5"))
    )
    (comp (ref "U16")
      (value "RT8010GQW")
      (footprint "WDFN-6_26_133X100_SMD")
      (description "Buck Switching Regulator IC Positive Adjustable 0.6V 1 Output 1A 6-WDFN Exposed Pad")
      (fields (field (name "MANUFACTURER") "Richtek USA Inc."))
      (libsource (lib "RK3399 _Module_Schlib") (part "REG-ADJ_5.5V-5.5V-1A-6-WDFN"))
    )
    (comp (ref "U17")
      (value "MP2143DJ-LF-Z")
      (footprint "SOT23-8")
      (description "Switching Voltage Regulators 3A, 5.5V, 1.2MHz Sync Stp-Dwn Swtchr")
      (fields (field (name "MANUFACTURER") "Monolithic Power Systems (MPS)"))
      (libsource (lib "RK3399 _Module_Schlib") (part "REG_0.6~5V-5.5V-3A-TSOT-23-8"))
    )
    (comp (ref "U18")
      (value "SYR838PKC")
      (footprint "CSP20_15.7_100x84_SMD")
      (description "Step-Down Positive Programmable 1 6A 2.4MHz CSP1.56*1.96-20 DC-DC Converters RoHS")
      (fields (field (name "MANUFACTURER") "Silergy Corp"))
      (libsource (lib "RK3399 _Module_Schlib") (part "IC_SYR838PKC"))
    )
    (comp (ref "U19")
      (value "RT8010GQW")
      (footprint "WDFN-6_26_133X100_SMD")
      (description "Buck Switching Regulator IC Positive Adjustable 0.6V 1 Output 1A 6-WDFN Exposed Pad")
      (fields (field (name "MANUFACTURER") "Richtek USA Inc."))
      (libsource (lib "RK3399 _Module_Schlib") (part "REG-ADJ_5.5V-5.5V-1A-6-WDFN"))
    )
  )
  (nets
    (net (code "1") (name "CPU_B_SLEEP") (class "Default")
      (node (ref "U13") (pin "A1") (pinfunction "VSEL_A1") (pintype "passive"))
    )
    (net (code "2") (name "GND") (class "Default")
      (node (ref "C280") (pin "1") (pinfunction "1_1") (pintype "passive"))
      (node (ref "C281") (pin "1") (pinfunction "1_1") (pintype "passive"))
      (node (ref "C282") (pin "1") (pinfunction "1_1") (pintype "passive"))
      (node (ref "C283") (pin "1") (pinfunction "1_1") (pintype "passive"))
      (node (ref "C284") (pin "1") (pinfunction "1_1") (pintype "passive"))
      (node (ref "C285") (pin "1") (pinfunction "1_1") (pintype "passive"))
      (node (ref "C286") (pin "1") (pinfunction "1_1") (pintype "passive"))
      (node (ref "C287") (pin "1") (pinfunction "1_1") (pintype "passive"))
      (node (ref "C288") (pin "1") (pinfunction "1_1") (pintype "passive"))
      (node (ref "C289") (pin "1") (pinfunction "1_1") (pintype "passive"))
      (node (ref "C291") (pin "1") (pinfunction "1_1") (pintype "passive"))
      (node (ref "C292") (pin "1") (pinfunction "1_1") (pintype "passive"))
      (node (ref "C293") (pin "1") (pinfunction "1_1") (pintype "passive"))
      (node (ref "C294") (pin "1") (pinfunction "1_1") (pintype "passive"))
      (node (ref "C295") (pin "1") (pinfunction "1_1") (pintype "passive"))
      (node (ref "C296") (pin "1") (pinfunction "1_1") (pintype "passive"))
      (node (ref "C297") (pin "1") (pinfunction "1_1") (pintype "passive"))
      (node (ref "C299") (pin "1") (pinfunction "1_1") (pintype "passive"))
      (node (ref "C300") (pin "1") (pinfunction "1_1") (pintype "passive"))
      (node (ref "C301") (pin "1") (pinfunction "1_1") (pintype "passive"))
      (node (ref "C302") (pin "1") (pinfunction "1_1") (pintype "passive"))
      (node (ref "C303") (pin "1") (pinfunction "1_1") (pintype "passive"))
      (node (ref "C304") (pin "1") (pinfunction "1_1") (pintype "passive"))
      (node (ref "C305") (pin "1") (pinfunction "1_1") (pintype "passive"))
      (node (ref "C306") (pin "1") (pinfunction "1_1") (pintype "passive"))
      (node (ref "C307") (pin "1") (pinfunction "1_1") (pintype "passive"))
      (node (ref "C308") (pin "1") (pinfunction "1_1") (pintype "passive"))
      (node (ref "C309") (pin "1") (pinfunction "1_1") (pintype "passive"))
      (node (ref "C310") (pin "1") (pinfunction "1_1") (pintype "passive"))
      (node (ref "C311") (pin "1") (pinfunction "1_1") (pintype "passive"))
      (node (ref "C312") (pin "1") (pinfunction "1_1") (pintype "passive"))
      (node (ref "C313") (pin "1") (pinfunction "1_1") (pintype "passive"))
      (node (ref "C314") (pin "1") (pinfunction "1_1") (pintype "passive"))
      (node (ref "C315") (pin "1") (pinfunction "1_1") (pintype "passive"))
      (node (ref "C316") (pin "1") (pinfunction "1_1") (pintype "passive"))
      (node (ref "C317") (pin "1") (pinfunction "1_1") (pintype "passive"))
      (node (ref "C318") (pin "1") (pinfunction "1_1") (pintype "passive"))
      (node (ref "C319") (pin "1") (pinfunction "1_1") (pintype "passive"))
      (node (ref "C320") (pin "1") (pinfunction "1_1") (pintype "passive"))
      (node (ref "C321") (pin "1") (pinfunction "1_1") (pintype "passive"))
      (node (ref "J4") (pin "A12") (pinfunction "GND2_A12") (pintype "passive"))
      (node (ref "J4") (pin "B12") (pinfunction "GND1_B12") (pintype "passive"))
      (node (ref "J4") (pin "E1") (pinfunction "GND_E1_E1") (pintype "passive"))
      (node (ref "J4") (pin "E2") (pinfunction "GND_E2_E2") (pintype "passive"))
      (node (ref "J4") (pin "E3") (pinfunction "GND_E3_E3") (pintype "passive"))
      (node (ref "J4") (pin "E4") (pinfunction "GND_E4_E4") (pintype "passive"))
      (node (ref "Q4") (pin "2") (pinfunction "E_2") (pintype "passive"))
      (node (ref "R104") (pin "1") (pinfunction "1_1") (pintype "passive"))
      (node (ref "R105") (pin "2") (pinfunction "2_2") (pintype "passive"))
      (node (ref "R113") (pin "1") (pinfunction "1_1") (pintype "passive"))
      (node (ref "R114") (pin "1") (pinfunction "1_1") (pintype "passive"))
      (node (ref "R115") (pin "1") (pinfunction "1_1") (pintype "passive"))
      (node (ref "R120") (pin "1") (pinfunction "1_1") (pintype "passive"))
      (node (ref "R122") (pin "1") (pinfunction "1_1") (pintype "passive"))
      (node (ref "R96") (pin "1") (pinfunction "1_1") (pintype "passive"))
      (node (ref "R97") (pin "1") (pinfunction "1_1") (pintype "passive"))
      (node (ref "U13") (pin "B2") (pinfunction "GND1_B2") (pintype "passive"))
      (node (ref "U13") (pin "B3") (pinfunction "GND2_B3") (pintype "passive"))
      (node (ref "U13") (pin "B4") (pinfunction "AGND_B4") (pintype "passive"))
      (node (ref "U13") (pin "C1") (pinfunction "GND3_C1") (pintype "passive"))
      (node (ref "U13") (pin "C2") (pinfunction "GND4_C2") (pintype "passive"))
      (node (ref "U13") (pin "C3") (pinfunction "GND5_C3") (pintype "passive"))
      (node (ref "U13") (pin "C4") (pinfunction "GND6_C4") (pintype "passive"))
      (node (ref "U14") (pin "10") (pinfunction "AGND_10") (pintype "passive"))
      (node (ref "U14") (pin "2") (pinfunction "PGND_2") (pintype "passive"))
      (node (ref "U15") (pin "2") (pinfunction "GND_2") (pintype "passive"))
      (node (ref "U16") (pin "5") (pinfunction "GND_5") (pintype "passive"))
      (node (ref "U16") (pin "7") (pinfunction "PAD_7") (pintype "passive"))
      (node (ref "U17") (pin "4") (pinfunction "PGND_4") (pintype "passive"))
      (node (ref "U17") (pin "6") (pinfunction "AGND_6") (pintype "passive"))
      (node (ref "U18") (pin "B2") (pinfunction "GND1_B2") (pintype "passive"))
      (node (ref "U18") (pin "B3") (pinfunction "GND2_B3") (pintype "passive"))
      (node (ref "U18") (pin "B4") (pinfunction "AGND_B4") (pintype "passive"))
      (node (ref "U18") (pin "C1") (pinfunction "GND3_C1") (pintype "passive"))
      (node (ref "U18") (pin "C2") (pinfunction "GND4_C2") (pintype "passive"))
      (node (ref "U18") (pin "C3") (pinfunction "GND5_C3") (pintype "passive"))
      (node (ref "U18") (pin "C4") (pinfunction "GND6_C4") (pintype "passive"))
      (node (ref "U19") (pin "5") (pinfunction "GND_5") (pintype "passive"))
      (node (ref "U19") (pin "7") (pinfunction "PAD_7") (pintype "passive"))
    )
    (net (code "3") (name "GPU_SLEEP") (class "Default")
      (node (ref "U18") (pin "A1") (pinfunction "VSEL_A1") (pintype "passive"))
    )
    (net (code "4") (name "I2C_SCL_PMIC") (class "Default")
      (node (ref "U13") (pin "A3") (pinfunction "SCL_A3") (pintype "passive"))
      (node (ref "U18") (pin "A3") (pinfunction "SCL_A3") (pintype "passive"))
    )
    (net (code "5") (name "I2C_SDA_PMIC") (class "Default")
      (node (ref "U13") (pin "B1") (pinfunction "SDA_B1") (pintype "passive"))
      (node (ref "U18") (pin "B1") (pinfunction "SDA_B1") (pintype "passive"))
    )
    (net (code "6") (name "LOG_DVS_PWM") (class "Default")
      (node (ref "R109") (pin "1") (pinfunction "1_1") (pintype "passive"))
      (node (ref "R112") (pin "2") (pinfunction "2_2") (pintype "passive"))
    )
    (net (code "7") (name "Net-(C290-Pad2)") (class "Default")
      (node (ref "C290") (pin "2") (pinfunction "2_2") (pintype "passive"))
      (node (ref "R98") (pin "2") (pinfunction "2_2") (pintype "passive"))
    )
    (net (code "8") (name "Net-(C312-Pad2)") (class "Default")
      (node (ref "C312") (pin "2") (pinfunction "2_2") (pintype "passive"))
      (node (ref "R109") (pin "2") (pinfunction "2_2") (pintype "passive"))
      (node (ref "R110") (pin "2") (pinfunction "2_2") (pintype "passive"))
      (node (ref "R113") (pin "2") (pinfunction "2_2") (pintype "passive"))
    )
    (net (code "9") (name "Net-(J4-CC1)") (class "Default")
      (node (ref "J4") (pin "A5") (pinfunction "CC1_A5") (pintype "passive"))
      (node (ref "R96") (pin "2") (pinfunction "2_2") (pintype "passive"))
    )
    (net (code "10") (name "Net-(J4-CC2)") (class "Default")
      (node (ref "J4") (pin "B5") (pinfunction "CC2_B5") (pintype "passive"))
      (node (ref "R97") (pin "2") (pinfunction "2_2") (pintype "passive"))
    )
    (net (code "11") (name "Net-(Q2-D)") (class "Default")
      (node (ref "C292") (pin "2") (pinfunction "2_2") (pintype "passive"))
      (node (ref "C293") (pin "2") (pinfunction "2_2") (pintype "passive"))
      (node (ref "C294") (pin "2") (pinfunction "2_2") (pintype "passive"))
      (node (ref "Q2") (pin "5") (pinfunction "D_5") (pintype "passive"))
      (node (ref "R101") (pin "2") (pinfunction "2_2") (pintype "passive"))
      (node (ref "U14") (pin "1") (pinfunction "VIN_1") (pintype "passive"))
    )
    (net (code "12") (name "Net-(Q2-G)") (class "Default")
      (node (ref "C298") (pin "2") (pinfunction "2_2") (pintype "passive"))
      (node (ref "Q2") (pin "4") (pinfunction "G_4") (pintype "passive"))
      (node (ref "R102") (pin "2") (pinfunction "2_2") (pintype "passive"))
      (node (ref "R104") (pin "2") (pinfunction "2_2") (pintype "passive"))
    )
    (net (code "13") (name "Net-(Q3-G)") (class "Default")
      (node (ref "Q3") (pin "1") (pinfunction "G_1") (pintype "passive"))
      (node (ref "Q4") (pin "3") (pinfunction "C_3") (pintype "passive"))
      (node (ref "R118") (pin "2") (pinfunction "2_2") (pintype "passive"))
    )
    (net (code "14") (name "Net-(Q4-B)") (class "Default")
      (node (ref "Q4") (pin "1") (pinfunction "B_1") (pintype "passive"))
      (node (ref "R119") (pin "1") (pinfunction "1_1") (pintype "passive"))
      (node (ref "R120") (pin "2") (pinfunction "2_2") (pintype "passive"))
    )
    (net (code "15") (name "Net-(U13-EN)") (class "Default")
      (node (ref "C291") (pin "2") (pinfunction "2_2") (pintype "passive"))
      (node (ref "R99") (pin "1") (pinfunction "1_1") (pintype "passive"))
      (node (ref "U13") (pin "A2") (pinfunction "EN_A2") (pintype "passive"))
    )
    (net (code "16") (name "Net-(U13-SW_1)") (class "Default")
      (node (ref "L2") (pin "1") (pinfunction "1_1") (pintype "passive"))
      (node (ref "U13") (pin "D3") (pinfunction "SW_1_D3") (pintype "passive"))
      (node (ref "U13") (pin "D4") (pinfunction "SW_2_D4") (pintype "passive"))
      (node (ref "U13") (pin "E3") (pinfunction "SW_3_E3") (pintype "passive"))
      (node (ref "U13") (pin "E4") (pinfunction "SW_4_E4") (pintype "passive"))
    )
    (net (code "17") (name "Net-(U14-BST)") (class "Default")
      (node (ref "R98") (pin "1") (pinfunction "1_1") (pintype "passive"))
      (node (ref "U14") (pin "8") (pinfunction "BST_8") (pintype "passive"))
    )
    (net (code "18") (name "Net-(U14-EN)") (class "Default")
      (node (ref "R103") (pin "1") (pinfunction "1_1") (pintype "passive"))
      (node (ref "R105") (pin "1") (pinfunction "1_1") (pintype "passive"))
      (node (ref "U14") (pin "11") (pinfunction "EN_11") (pintype "passive"))
    )
    (net (code "19") (name "Net-(U14-EN_CLK)") (class "Default")
      (node (ref "R101") (pin "1") (pinfunction "1_1") (pintype "passive"))
      (node (ref "U14") (pin "12") (pinfunction "EN_CLK_12") (pintype "passive"))
    )
    (net (code "20") (name "Net-(U14-LDO)") (class "Default")
      (node (ref "C305") (pin "2") (pinfunction "2_2") (pintype "passive"))
      (node (ref "U14") (pin "6") (pinfunction "LDO_6") (pintype "passive"))
      (node (ref "U15") (pin "1") (pinfunction "VIN_1") (pintype "passive"))
      (node (ref "U15") (pin "3") (pinfunction "EN_3") (pintype "passive"))
    )
    (net (code "21") (name "Net-(U14-PG)") (class "Default")
      (node (ref "R106") (pin "2") (pinfunction "2_2") (pintype "passive"))
      (node (ref "U14") (pin "3") (pinfunction "PG_3") (pintype "passive"))
    )
    (net (code "22") (name "Net-(U14-SW)") (class "Default")
      (node (ref "C290") (pin "1") (pinfunction "1_1") (pintype "passive"))
      (node (ref "L3") (pin "1") (pinfunction "1_1") (pintype "passive"))
      (node (ref "U14") (pin "7") (pinfunction "SW_7") (pintype "passive"))
    )
    (net (code "23") (name "Net-(U14-VCC)") (class "Default")
      (node (ref "C299") (pin "2") (pinfunction "2_2") (pintype "passive"))
      (node (ref "R106") (pin "1") (pinfunction "1_1") (pintype "passive"))
      (node (ref "U14") (pin "9") (pinfunction "VCC_9") (pintype "passive"))
    )
    (net (code "24") (name "Net-(U16-EN)") (class "Default")
      (node (ref "C307") (pin "2") (pinfunction "2_2") (pintype "passive"))
      (node (ref "R108") (pin "2") (pinfunction "2_2") (pintype "passive"))
      (node (ref "U16") (pin "2") (pinfunction "EN_2") (pintype "passive"))
    )
    (net (code "25") (name "Net-(U16-FB)") (class "Default")
      (node (ref "R107") (pin "1") (pinfunction "1_1") (pintype "passive"))
      (node (ref "R110") (pin "1") (pinfunction "1_1") (pintype "passive"))
      (node (ref "R114") (pin "2") (pinfunction "2_2") (pintype "passive"))
      (node (ref "U16") (pin "6") (pinfunction "FB_6") (pintype "passive"))
    )
    (net (code "26") (name "Net-(U16-LX)") (class "Default")
      (node (ref "L4") (pin "1") (pinfunction "1_1") (pintype "passive"))
      (node (ref "U16") (pin "4") (pinfunction "LX_4") (pintype "passive"))
    )
    (net (code "27") (name "Net-(U17-FB)") (class "Default")
      (node (ref "R111") (pin "1") (pinfunction "1_1") (pintype "passive"))
      (node (ref "R115") (pin "2") (pinfunction "2_2") (pintype "passive"))
      (node (ref "U17") (pin "7") (pinfunction "FB_7") (pintype "passive"))
    )
    (net (code "28") (name "Net-(U17-SW)") (class "Default")
      (node (ref "L5") (pin "1") (pinfunction "1_1") (pintype "passive"))
      (node (ref "U17") (pin "3") (pinfunction "SW_3") (pintype "passive"))
    )
    (net (code "29") (name "Net-(U18-EN)") (class "Default")
      (node (ref "C319") (pin "2") (pinfunction "2_2") (pintype "passive"))
      (node (ref "R116") (pin "1") (pinfunction "1_1") (pintype "passive"))
      (node (ref "U18") (pin "A2") (pinfunction "EN_A2") (pintype "passive"))
    )
    (net (code "30") (name "Net-(U18-SW_1)") (class "Default")
      (node (ref "L6") (pin "1") (pinfunction "1_1") (pintype "passive"))
      (node (ref "U18") (pin "D3") (pinfunction "SW_1_D3") (pintype "passive"))
      (node (ref "U18") (pin "D4") (pinfunction "SW_2_D4") (pintype "passive"))
      (node (ref "U18") (pin "E3") (pinfunction "SW_3_E3") (pintype "passive"))
      (node (ref "U18") (pin "E4") (pinfunction "SW_4_E4") (pintype "passive"))
    )
    (net (code "31") (name "Net-(U19-FB)") (class "Default")
      (node (ref "R121") (pin "1") (pinfunction "1_1") (pintype "passive"))
      (node (ref "R122") (pin "2") (pinfunction "2_2") (pintype "passive"))
      (node (ref "U19") (pin "6") (pinfunction "FB_6") (pintype "passive"))
    )
    (net (code "32") (name "Net-(U19-LX)") (class "Default")
      (node (ref "L7") (pin "1") (pinfunction "1_1") (pintype "passive"))
      (node (ref "U19") (pin "4") (pinfunction "LX_4") (pintype "passive"))
    )
    (net (code "33") (name "OTP_OUT_H") (class "Default")
      (node (ref "R119") (pin "2") (pinfunction "2_2") (pintype "passive"))
    )
    (net (code "34") (name "PMIC_EXT_EN") (class "Default")
      (node (ref "R103") (pin "2") (pinfunction "2_2") (pintype "passive"))
      (node (ref "U17") (pin "8") (pinfunction "EN_8") (pintype "passive"))
      (node (ref "U19") (pin "2") (pinfunction "EN_2") (pintype "passive"))
    )
    (net (code "35") (name "RESET_IN_H") (class "Default")
      (node (ref "Q3") (pin "3") (pinfunction "D_3") (pintype "passive"))
    )
    (net (code "36") (name "VCC3V3_S5") (class "Default")
      (node (ref "C300") (pin "2") (pinfunction "2_2") (pintype "passive"))
      (node (ref "C301") (pin "2") (pinfunction "2_2") (pintype "passive"))
      (node (ref "C302") (pin "2") (pinfunction "2_2") (pintype "passive"))
      (node (ref "U15") (pin "5") (pinfunction "VOUT_5") (pintype "passive"))
    )
    (net (code "37") (name "VCC3V3_SYS") (class "Default")
      (node (ref "C283") (pin "2") (pinfunction "2_2") (pintype "passive"))
      (node (ref "C284") (pin "2") (pinfunction "2_2") (pintype "passive"))
      (node (ref "C285") (pin "2") (pinfunction "2_2") (pintype "passive"))
      (node (ref "C303") (pin "2") (pinfunction "2_2") (pintype "passive"))
      (node (ref "C304") (pin "2") (pinfunction "2_2") (pintype "passive"))
      (node (ref "C310") (pin "2") (pinfunction "2_2") (pintype "passive"))
      (node (ref "C311") (pin "2") (pinfunction "2_2") (pintype "passive"))
      (node (ref "C313") (pin "2") (pinfunction "2_2") (pintype "passive"))
      (node (ref "C314") (pin "2") (pinfunction "2_2") (pintype "passive"))
      (node (ref "C315") (pin "2") (pinfunction "2_2") (pintype "passive"))
      (node (ref "C320") (pin "2") (pinfunction "2_2") (pintype "passive"))
      (node (ref "L5") (pin "2") (pinfunction "2_2") (pintype "passive"))
      (node (ref "Q3") (pin "2") (pinfunction "S_2") (pintype "passive"))
      (node (ref "R111") (pin "2") (pinfunction "2_2") (pintype "passive"))
      (node (ref "R118") (pin "1") (pinfunction "1_1") (pintype "passive"))
      (node (ref "U13") (pin "D1") (pinfunction "VIN_1_D1") (pintype "passive"))
      (node (ref "U13") (pin "D2") (pinfunction "VIN_2_D2") (pintype "passive"))
      (node (ref "U13") (pin "E1") (pinfunction "VIN_3_E1") (pintype "passive"))
      (node (ref "U13") (pin "E2") (pinfunction "VIN_4_E2") (pintype "passive"))
      (node (ref "U16") (pin "3") (pinfunction "VIN_3") (pintype "passive"))
      (node (ref "U17") (pin "5") (pinfunction "OUT_5") (pintype "passive"))
      (node (ref "U18") (pin "D1") (pinfunction "VIN_1_D1") (pintype "passive"))
      (node (ref "U18") (pin "D2") (pinfunction "VIN_2_D2") (pintype "passive"))
      (node (ref "U18") (pin "E1") (pinfunction "VIN_3_E1") (pintype "passive"))
      (node (ref "U18") (pin "E2") (pinfunction "VIN_4_E2") (pintype "passive"))
      (node (ref "U19") (pin "3") (pinfunction "VIN_3") (pintype "passive"))
    )
    (net (code "38") (name "VCC5V0_CORE") (class "Default")
      (node (ref "C308") (pin "2") (pinfunction "2_2") (pintype "passive"))
      (node (ref "C309") (pin "2") (pinfunction "2_2") (pintype "passive"))
      (node (ref "U17") (pin "2") (pinfunction "VIN_2") (pintype "passive"))
    )
    (net (code "39") (name "VCC5V0_SYS") (class "Default")
      (node (ref "C295") (pin "2") (pinfunction "2_2") (pintype "passive"))
      (node (ref "C296") (pin "2") (pinfunction "2_2") (pintype "passive"))
      (node (ref "C297") (pin "2") (pinfunction "2_2") (pintype "passive"))
      (node (ref "L3") (pin "2") (pinfunction "2_2") (pintype "passive"))
      (node (ref "U14") (pin "5") (pinfunction "VOUT_5") (pintype "passive"))
    )
    (net (code "40") (name "VCC_0V9") (class "Default")
      (node (ref "C321") (pin "2") (pinfunction "2_2") (pintype "passive"))
      (node (ref "L7") (pin "2") (pinfunction "2_2") (pintype "passive"))
      (node (ref "R121") (pin "2") (pinfunction "2_2") (pintype "passive"))
    )
    (net (code "41") (name "VCC_1V8") (class "Default")
      (node (ref "R108") (pin "1") (pinfunction "1_1") (pintype "passive"))
      (node (ref "R116") (pin "2") (pinfunction "2_2") (pintype "passive"))
      (node (ref "R99") (pin "2") (pinfunction "2_2") (pintype "passive"))
    )
    (net (code "42") (name "VCC_3V0") (class "Default")
      (node (ref "R112") (pin "1") (pinfunction "1_1") (pintype "passive"))
    )
    (net (code "43") (name "VCC_IN_CONN") (class "Default")
      (node (ref "C280") (pin "2") (pinfunction "2_2") (pintype "passive"))
      (node (ref "C281") (pin "2") (pinfunction "2_2") (pintype "passive"))
      (node (ref "C282") (pin "2") (pinfunction "2_2") (pintype "passive"))
      (node (ref "C298") (pin "1") (pinfunction "1_1") (pintype "passive"))
      (node (ref "J4") (pin "A9") (pinfunction "VBUS_2_A9") (pintype "passive"))
      (node (ref "J4") (pin "B9") (pinfunction "VBUS_1_B9") (pintype "passive"))
      (node (ref "Q2") (pin "1") (pinfunction "S_1") (pintype "passive"))
      (node (ref "Q2") (pin "2") (pinfunction "S_2") (pintype "passive"))
      (node (ref "Q2") (pin "3") (pinfunction "S_3") (pintype "passive"))
      (node (ref "R102") (pin "1") (pinfunction "1_1") (pintype "passive"))
    )
    (net (code "44") (name "VDD_CPU_B") (class "Default")
      (node (ref "C286") (pin "2") (pinfunction "2_2") (pintype "passive"))
      (node (ref "C287") (pin "2") (pinfunction "2_2") (pintype "passive"))
      (node (ref "C288") (pin "2") (pinfunction "2_2") (pintype "passive"))
      (node (ref "C289") (pin "2") (pinfunction "2_2") (pintype "passive"))
      (node (ref "L2") (pin "2") (pinfunction "2_2") (pintype "passive"))
      (node (ref "R100") (pin "2") (pinfunction "2_2") (pintype "passive"))
    )
    (net (code "45") (name "VDD_CPU_B_FB") (class "Default")
      (node (ref "R100") (pin "1") (pinfunction "1_1") (pintype "passive"))
      (node (ref "U13") (pin "A4") (pinfunction "VOUT_A4") (pintype "passive"))
    )
    (net (code "46") (name "VDD_GPU") (class "Default")
      (node (ref "C316") (pin "2") (pinfunction "2_2") (pintype "passive"))
      (node (ref "C317") (pin "2") (pinfunction "2_2") (pintype "passive"))
      (node (ref "C318") (pin "2") (pinfunction "2_2") (pintype "passive"))
      (node (ref "L6") (pin "2") (pinfunction "2_2") (pintype "passive"))
      (node (ref "R117") (pin "1") (pinfunction "1_1") (pintype "passive"))
    )
    (net (code "47") (name "VDD_GPU_FB") (class "Default")
      (node (ref "R117") (pin "2") (pinfunction "2_2") (pintype "passive"))
      (node (ref "U18") (pin "A4") (pinfunction "VOUT_A4") (pintype "passive"))
    )
    (net (code "48") (name "VDD_LOG") (class "Default")
      (node (ref "C306") (pin "2") (pinfunction "2_2") (pintype "passive"))
      (node (ref "L4") (pin "2") (pinfunction "2_2") (pintype "passive"))
      (node (ref "R107") (pin "2") (pinfunction "2_2") (pintype "passive"))
    )
    (net (code "49") (name "unconnected-(U14-CLK-Pad4)") (class "Default")
      (node (ref "U14") (pin "4") (pinfunction "CLK_4") (pintype "passive+no_connect"))
    )
    (net (code "50") (name "unconnected-(U15-BP-Pad4)") (class "Default")
      (node (ref "U15") (pin "4") (pinfunction "BP_4") (pintype "passive+no_connect"))
    )
    (net (code "51") (name "unconnected-(U16-NC-Pad1)") (class "Default")
      (node (ref "U16") (pin "1") (pinfunction "NC_1") (pintype "passive+no_connect"))
    )
    (net (code "52") (name "unconnected-(U17-PG-Pad1)") (class "Default")
      (node (ref "U17") (pin "1") (pinfunction "PG_1") (pintype "passive+no_connect"))
    )
    (net (code "53") (name "unconnected-(U19-NC-Pad1)") (class "Default")
      (node (ref "U19") (pin "1") (pinfunction "NC_1") (pintype "passive+no_connect"))
    )
  )
)
